# superteensy.net
KiCad netlist of a schematic drawn in EAGLE
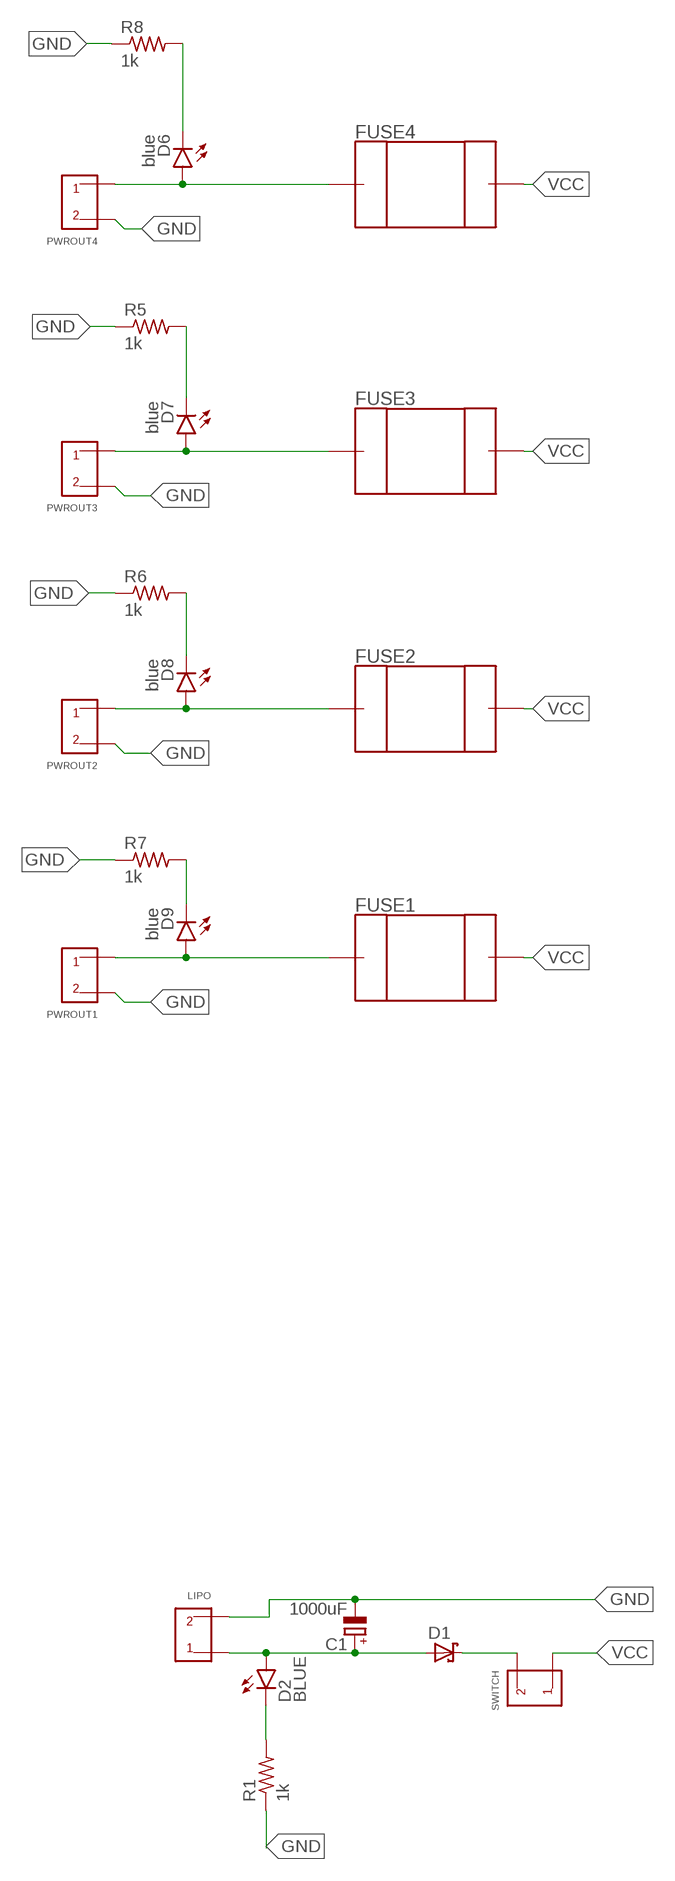
[diagram p0: schematic, sheet 1, part 1 of 2]
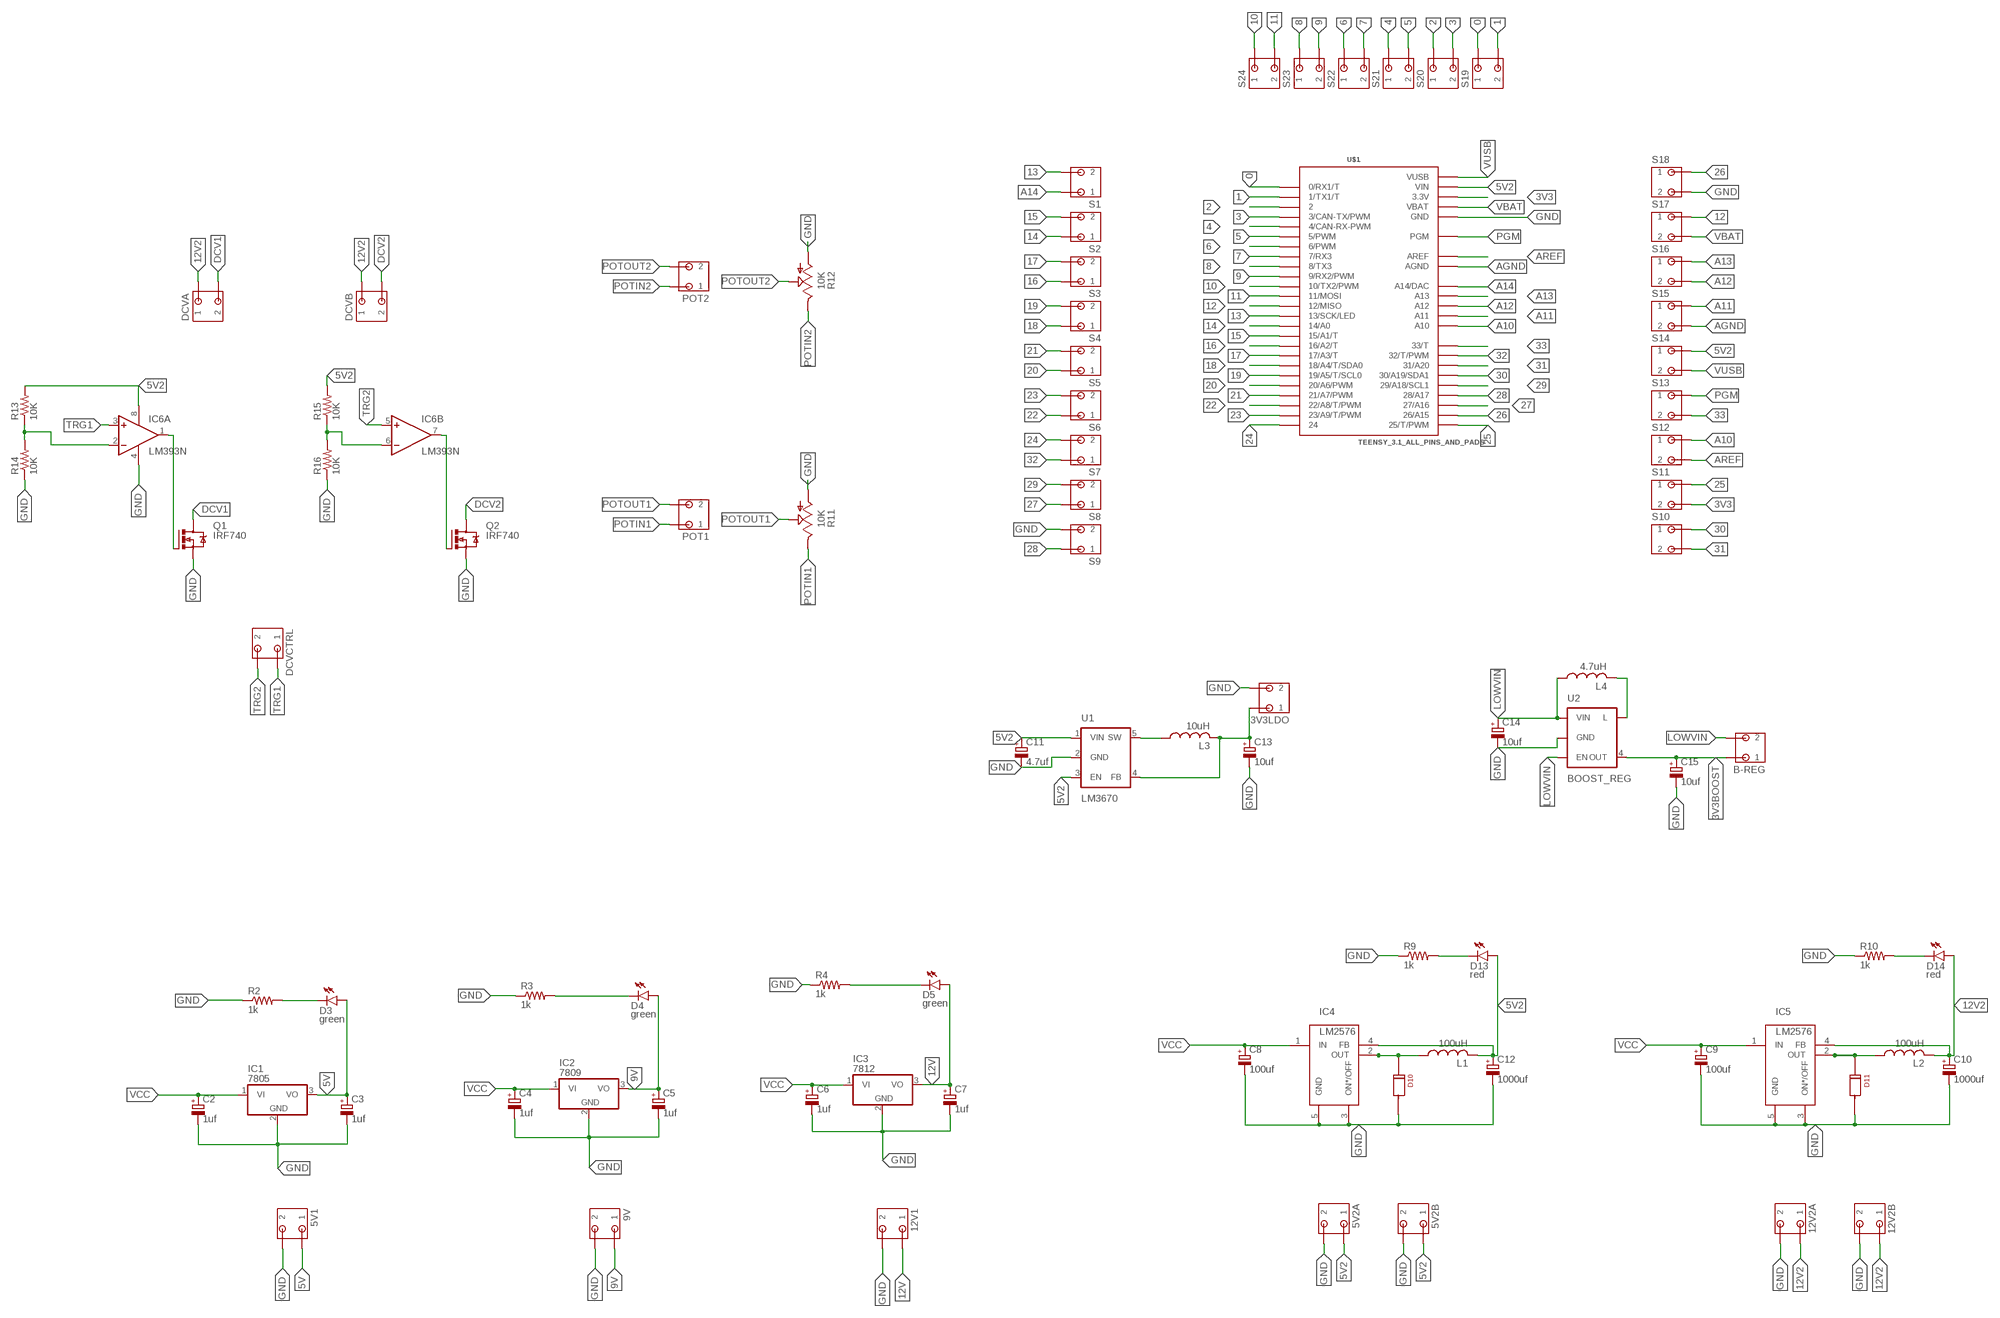
[diagram p1: schematic, sheet 1, part 2 of 2]

(export (version "E")
  (design (tool "Eeschema 10.0.6"))
  (components
    (comp (ref "3V3LDO")
      (value "SPTBA2-B2")
      (footprint "eagle-import:SPTB")
      (libsource (lib "eagle-import") (part "SPTBA2-B2"))
    )
    (comp (ref "5V1")
      (value "SPTBA2-B2")
      (footprint "eagle-import:SPTB")
      (libsource (lib "eagle-import") (part "SPTBA2-B2"))
    )
    (comp (ref "5V2A")
      (value "SPTBA2-B2")
      (footprint "eagle-import:SPTB")
      (libsource (lib "eagle-import") (part "SPTBA2-B2"))
    )
    (comp (ref "5V2B")
      (value "SPTBA2-B2")
      (footprint "eagle-import:SPTB")
      (libsource (lib "eagle-import") (part "SPTBA2-B2"))
    )
    (comp (ref "9V")
      (value "SPTBA2-B2")
      (footprint "eagle-import:SPTB")
      (libsource (lib "eagle-import") (part "SPTBA2-B2"))
    )
    (comp (ref "12V1")
      (value "SPTBA2-B2")
      (footprint "eagle-import:SPTB")
      (libsource (lib "eagle-import") (part "SPTBA2-B2"))
    )
    (comp (ref "12V2A")
      (value "SPTBA2-B2")
      (footprint "eagle-import:SPTB")
      (libsource (lib "eagle-import") (part "SPTBA2-B2"))
    )
    (comp (ref "12V2B")
      (value "SPTBA2-B2")
      (footprint "eagle-import:SPTB")
      (libsource (lib "eagle-import") (part "SPTBA2-B2"))
    )
    (comp (ref "B-REG")
      (value "SPTBA2-B2")
      (footprint "eagle-import:SPTB")
      (libsource (lib "eagle-import") (part "SPTBA2-B2"))
    )
    (comp (ref "C1")
      (value "1000uF")
      (footprint "eagle-import:E7,5-16")
      (libsource (lib "eagle-import") (part "CPOL-EUE7.5-16"))
    )
    (comp (ref "C2")
      (value "1uf")
      (footprint "eagle-import:E2-5")
      (libsource (lib "eagle-import") (part "CPOL-EUE2-5"))
    )
    (comp (ref "C3")
      (value "1uf")
      (footprint "eagle-import:E2-5")
      (libsource (lib "eagle-import") (part "CPOL-EUE2-5"))
    )
    (comp (ref "C4")
      (value "1uf")
      (footprint "eagle-import:E2-5")
      (libsource (lib "eagle-import") (part "CPOL-EUE2-5"))
    )
    (comp (ref "C5")
      (value "1uf")
      (footprint "eagle-import:E2-5")
      (libsource (lib "eagle-import") (part "CPOL-EUE2-5"))
    )
    (comp (ref "C6")
      (value "1uf")
      (footprint "eagle-import:E2-5")
      (libsource (lib "eagle-import") (part "CPOL-EUE2-5"))
    )
    (comp (ref "C7")
      (value "1uf")
      (footprint "eagle-import:E2-5")
      (libsource (lib "eagle-import") (part "CPOL-EUE2-5"))
    )
    (comp (ref "C8")
      (value "100uf")
      (footprint "eagle-import:E2,5-6E")
      (libsource (lib "eagle-import") (part "CPOL-EUE2,5-6E"))
    )
    (comp (ref "C9")
      (value "100uf")
      (footprint "eagle-import:E2,5-6E")
      (libsource (lib "eagle-import") (part "CPOL-EUE2,5-6E"))
    )
    (comp (ref "C10")
      (value "1000uf")
      (footprint "eagle-import:E7,5-16")
      (libsource (lib "eagle-import") (part "CPOL-EUE7.5-16"))
    )
    (comp (ref "C11")
      (value "4.7uf")
      (footprint "eagle-import:E2-5")
      (libsource (lib "eagle-import") (part "CPOL-EUE2-5"))
    )
    (comp (ref "C12")
      (value "1000uf")
      (footprint "eagle-import:E7,5-16")
      (libsource (lib "eagle-import") (part "CPOL-EUE7.5-16"))
    )
    (comp (ref "C13")
      (value "10uf")
      (footprint "eagle-import:E2-5")
      (libsource (lib "eagle-import") (part "CPOL-EUE2-5"))
    )
    (comp (ref "C14")
      (value "10uf")
      (footprint "eagle-import:E2-5")
      (libsource (lib "eagle-import") (part "CPOL-EUE2-5"))
    )
    (comp (ref "C15")
      (value "10uf")
      (footprint "eagle-import:E2-5")
      (libsource (lib "eagle-import") (part "CPOL-EUE2-5"))
    )
    (comp (ref "D1")
      (value "SCHOTTKY-DIODEP6T15")
      (footprint "eagle-import:P6T15")
      (libsource (lib "eagle-import") (part "SCHOTTKY-DIODEP6T15"))
    )
    (comp (ref "D2")
      (value "BLUE")
      (footprint "eagle-import:LED5MM")
      (libsource (lib "eagle-import") (part "LED5MM"))
    )
    (comp (ref "D3")
      (value "green")
      (footprint "eagle-import:LED5MM")
      (libsource (lib "eagle-import") (part "LED5MM"))
    )
    (comp (ref "D4")
      (value "green")
      (footprint "eagle-import:LED5MM")
      (libsource (lib "eagle-import") (part "LED5MM"))
    )
    (comp (ref "D5")
      (value "green")
      (footprint "eagle-import:LED5MM")
      (libsource (lib "eagle-import") (part "LED5MM"))
    )
    (comp (ref "D6")
      (value "blue")
      (footprint "eagle-import:LED5MM")
      (libsource (lib "eagle-import") (part "LED5MM"))
    )
    (comp (ref "D7")
      (value "blue")
      (footprint "eagle-import:LED5MM")
      (libsource (lib "eagle-import") (part "LED5MM"))
    )
    (comp (ref "D8")
      (value "blue")
      (footprint "eagle-import:LED5MM")
      (libsource (lib "eagle-import") (part "LED5MM"))
    )
    (comp (ref "D9")
      (value "blue")
      (footprint "eagle-import:LED5MM")
      (libsource (lib "eagle-import") (part "LED5MM"))
    )
    (comp (ref "D10")
      (value "1N5822")
      (footprint "eagle-import:1N5822")
      (libsource (lib "eagle-import") (part "1N5822"))
    )
    (comp (ref "D11")
      (value "1N5822")
      (footprint "eagle-import:1N5822")
      (libsource (lib "eagle-import") (part "1N5822"))
    )
    (comp (ref "D13")
      (value "red")
      (footprint "eagle-import:LED5MM")
      (libsource (lib "eagle-import") (part "LED5MM"))
    )
    (comp (ref "D14")
      (value "red")
      (footprint "eagle-import:LED5MM")
      (libsource (lib "eagle-import") (part "LED5MM"))
    )
    (comp (ref "DCVA")
      (value "SPTBA2-B2")
      (footprint "eagle-import:SPTB")
      (libsource (lib "eagle-import") (part "SPTBA2-B2"))
    )
    (comp (ref "DCVB")
      (value "SPTBA2-B2")
      (footprint "eagle-import:SPTB")
      (libsource (lib "eagle-import") (part "SPTBA2-B2"))
    )
    (comp (ref "DCVCTRL")
      (value "SPTBA2-B2")
      (footprint "eagle-import:SPTB")
      (libsource (lib "eagle-import") (part "#rcn-15-new-A2-b2-appended_SPTBA2-B2"))
    )
    (comp (ref "FUSE1")
      (value "CPT-FUSE")
      (footprint "eagle-import:CPT-FUSES")
      (libsource (lib "eagle-import") (part "CPT-FUSE"))
    )
    (comp (ref "FUSE2")
      (value "CPT-FUSE")
      (footprint "eagle-import:CPT-FUSES")
      (libsource (lib "eagle-import") (part "CPT-FUSE"))
    )
    (comp (ref "FUSE3")
      (value "CPT-FUSE")
      (footprint "eagle-import:CPT-FUSES")
      (libsource (lib "eagle-import") (part "CPT-FUSE"))
    )
    (comp (ref "FUSE4")
      (value "CPT-FUSE")
      (footprint "eagle-import:CPT-FUSES")
      (libsource (lib "eagle-import") (part "CPT-FUSE"))
    )
    (comp (ref "IC1")
      (value "7805")
      (footprint "eagle-import:78XX")
      (libsource (lib "eagle-import") (part "7805"))
    )
    (comp (ref "IC2")
      (value "7809")
      (footprint "eagle-import:78XX")
      (libsource (lib "eagle-import") (part "7809"))
    )
    (comp (ref "IC3")
      (value "7812")
      (footprint "eagle-import:78XX")
      (libsource (lib "eagle-import") (part "7812"))
    )
    (comp (ref "IC4")
      (value "LM2576")
      (footprint "eagle-import:LM2576")
      (libsource (lib "eagle-import") (part "LM2576"))
    )
    (comp (ref "IC5")
      (value "LM2576")
      (footprint "eagle-import:LM2576")
      (libsource (lib "eagle-import") (part "LM2576"))
    )
    (comp (ref "IC6")
      (value "LM393N")
      (footprint "eagle-import:DIL08")
      (libsource (lib "eagle-import") (part "LM393N"))
    )
    (comp (ref "L1")
      (value "100uH")
      (footprint "eagle-import:0204_7")
      (libsource (lib "eagle-import") (part "L-US0204/7"))
    )
    (comp (ref "L2")
      (value "100uH")
      (footprint "eagle-import:0204_7")
      (libsource (lib "eagle-import") (part "L-US0204/7"))
    )
    (comp (ref "L3")
      (value "10uH")
      (footprint "eagle-import:0204_7")
      (libsource (lib "eagle-import") (part "L-US0204/7"))
    )
    (comp (ref "L4")
      (value "4.7uH")
      (footprint "eagle-import:0204_7")
      (libsource (lib "eagle-import") (part "L-US0204/7"))
    )
    (comp (ref "LIPO")
      (value "SCREW_XT-60")
      (footprint "eagle-import:SCREW_XT-60")
      (libsource (lib "eagle-import") (part "SCREW_XT-60"))
    )
    (comp (ref "POT1")
      (value "SPTBA2-B2")
      (footprint "eagle-import:SPTB")
      (libsource (lib "eagle-import") (part "SPTBA2-B2"))
    )
    (comp (ref "POT2")
      (value "SPTBA2-B2")
      (footprint "eagle-import:SPTB")
      (libsource (lib "eagle-import") (part "SPTBA2-B2"))
    )
    (comp (ref "PWROUT1")
      (value "SCREW_XT-60")
      (footprint "eagle-import:SCREW_XT-60")
      (libsource (lib "eagle-import") (part "SCREW_XT-60"))
    )
    (comp (ref "PWROUT2")
      (value "SCREW_XT-60")
      (footprint "eagle-import:SCREW_XT-60")
      (libsource (lib "eagle-import") (part "SCREW_XT-60"))
    )
    (comp (ref "PWROUT3")
      (value "SCREW_XT-60")
      (footprint "eagle-import:SCREW_XT-60")
      (libsource (lib "eagle-import") (part "SCREW_XT-60"))
    )
    (comp (ref "PWROUT4")
      (value "SCREW_XT-60")
      (footprint "eagle-import:SCREW_XT-60")
      (libsource (lib "eagle-import") (part "SCREW_XT-60"))
    )
    (comp (ref "Q1")
      (value "IRF740")
      (footprint "eagle-import:TO220BV")
      (libsource (lib "eagle-import") (part "IRF740"))
    )
    (comp (ref "Q2")
      (value "IRF740")
      (footprint "eagle-import:TO220BV")
      (libsource (lib "eagle-import") (part "IRF740"))
    )
    (comp (ref "R1")
      (value "1k")
      (footprint "eagle-import:0204_7")
      (libsource (lib "eagle-import") (part "R-US_0204/7"))
    )
    (comp (ref "R2")
      (value "1k")
      (footprint "eagle-import:0204_7")
      (libsource (lib "eagle-import") (part "R-US_0204/7"))
    )
    (comp (ref "R3")
      (value "1k")
      (footprint "eagle-import:0204_7")
      (libsource (lib "eagle-import") (part "R-US_0204/7"))
    )
    (comp (ref "R4")
      (value "1k")
      (footprint "eagle-import:0204_7")
      (libsource (lib "eagle-import") (part "R-US_0204/7"))
    )
    (comp (ref "R5")
      (value "1k")
      (footprint "eagle-import:0204_7")
      (libsource (lib "eagle-import") (part "R-US_0204/7"))
    )
    (comp (ref "R6")
      (value "1k")
      (footprint "eagle-import:0204_7")
      (libsource (lib "eagle-import") (part "R-US_0204/7"))
    )
    (comp (ref "R7")
      (value "1k")
      (footprint "eagle-import:0204_7")
      (libsource (lib "eagle-import") (part "R-US_0204/7"))
    )
    (comp (ref "R8")
      (value "1k")
      (footprint "eagle-import:0204_7")
      (libsource (lib "eagle-import") (part "R-US_0204/7"))
    )
    (comp (ref "R9")
      (value "1k")
      (footprint "eagle-import:0204_7")
      (libsource (lib "eagle-import") (part "R-US_0204/7"))
    )
    (comp (ref "R10")
      (value "1k")
      (footprint "eagle-import:0204_7")
      (libsource (lib "eagle-import") (part "R-US_0204/7"))
    )
    (comp (ref "R11")
      (value "10K")
      (footprint "eagle-import:CA6V")
      (libsource (lib "eagle-import") (part "TRIM_US-CA6V"))
    )
    (comp (ref "R12")
      (value "10K")
      (footprint "eagle-import:CA6V")
      (libsource (lib "eagle-import") (part "TRIM_US-CA6V"))
    )
    (comp (ref "R13")
      (value "10K")
      (footprint "eagle-import:0204_7")
      (libsource (lib "eagle-import") (part "R-US_0204/7"))
    )
    (comp (ref "R14")
      (value "10K")
      (footprint "eagle-import:0204_7")
      (libsource (lib "eagle-import") (part "R-US_0204/7"))
    )
    (comp (ref "R15")
      (value "10K")
      (footprint "eagle-import:0204_7")
      (libsource (lib "eagle-import") (part "R-US_0204/7"))
    )
    (comp (ref "R16")
      (value "10K")
      (footprint "eagle-import:0204_7")
      (libsource (lib "eagle-import") (part "R-US_0204/7"))
    )
    (comp (ref "S1")
      (value "SPTBA2-B2")
      (footprint "eagle-import:SPTB")
      (libsource (lib "eagle-import") (part "SPTBA2-B2"))
    )
    (comp (ref "S2")
      (value "SPTBA2-B2")
      (footprint "eagle-import:SPTB")
      (libsource (lib "eagle-import") (part "SPTBA2-B2"))
    )
    (comp (ref "S3")
      (value "SPTBA2-B2")
      (footprint "eagle-import:SPTB")
      (libsource (lib "eagle-import") (part "SPTBA2-B2"))
    )
    (comp (ref "S4")
      (value "SPTBA2-B2")
      (footprint "eagle-import:SPTB")
      (libsource (lib "eagle-import") (part "SPTBA2-B2"))
    )
    (comp (ref "S5")
      (value "SPTBA2-B2")
      (footprint "eagle-import:SPTB")
      (libsource (lib "eagle-import") (part "SPTBA2-B2"))
    )
    (comp (ref "S6")
      (value "SPTBA2-B2")
      (footprint "eagle-import:SPTB")
      (libsource (lib "eagle-import") (part "SPTBA2-B2"))
    )
    (comp (ref "S7")
      (value "SPTBA2-B2")
      (footprint "eagle-import:SPTB")
      (libsource (lib "eagle-import") (part "SPTBA2-B2"))
    )
    (comp (ref "S8")
      (value "SPTBA2-B2")
      (footprint "eagle-import:SPTB")
      (libsource (lib "eagle-import") (part "SPTBA2-B2"))
    )
    (comp (ref "S9")
      (value "SPTBA2-B2")
      (footprint "eagle-import:SPTB")
      (libsource (lib "eagle-import") (part "SPTBA2-B2"))
    )
    (comp (ref "S10")
      (value "SPTBA2-B2")
      (footprint "eagle-import:SPTB")
      (libsource (lib "eagle-import") (part "SPTBA2-B2"))
    )
    (comp (ref "S11")
      (value "SPTBA2-B2")
      (footprint "eagle-import:SPTB")
      (libsource (lib "eagle-import") (part "SPTBA2-B2"))
    )
    (comp (ref "S12")
      (value "SPTBA2-B2")
      (footprint "eagle-import:SPTB")
      (libsource (lib "eagle-import") (part "SPTBA2-B2"))
    )
    (comp (ref "S13")
      (value "SPTBA2-B2")
      (footprint "eagle-import:SPTB")
      (libsource (lib "eagle-import") (part "SPTBA2-B2"))
    )
    (comp (ref "S14")
      (value "SPTBA2-B2")
      (footprint "eagle-import:SPTB")
      (libsource (lib "eagle-import") (part "SPTBA2-B2"))
    )
    (comp (ref "S15")
      (value "SPTBA2-B2")
      (footprint "eagle-import:SPTB")
      (libsource (lib "eagle-import") (part "SPTBA2-B2"))
    )
    (comp (ref "S16")
      (value "SPTBA2-B2")
      (footprint "eagle-import:SPTB")
      (libsource (lib "eagle-import") (part "SPTBA2-B2"))
    )
    (comp (ref "S17")
      (value "SPTBA2-B2")
      (footprint "eagle-import:SPTB")
      (libsource (lib "eagle-import") (part "SPTBA2-B2"))
    )
    (comp (ref "S18")
      (value "SPTBA2-B2")
      (footprint "eagle-import:SPTB")
      (libsource (lib "eagle-import") (part "SPTBA2-B2"))
    )
    (comp (ref "S19")
      (value "SPTBA2-B2")
      (footprint "eagle-import:SPTB")
      (libsource (lib "eagle-import") (part "SPTBA2-B2"))
    )
    (comp (ref "S20")
      (value "SPTBA2-B2")
      (footprint "eagle-import:SPTB")
      (libsource (lib "eagle-import") (part "SPTBA2-B2"))
    )
    (comp (ref "S21")
      (value "SPTBA2-B2")
      (footprint "eagle-import:SPTB")
      (libsource (lib "eagle-import") (part "SPTBA2-B2"))
    )
    (comp (ref "S22")
      (value "SPTBA2-B2")
      (footprint "eagle-import:SPTB")
      (libsource (lib "eagle-import") (part "SPTBA2-B2"))
    )
    (comp (ref "S23")
      (value "SPTBA2-B2")
      (footprint "eagle-import:SPTB")
      (libsource (lib "eagle-import") (part "SPTBA2-B2"))
    )
    (comp (ref "S24")
      (value "SPTBA2-B2")
      (footprint "eagle-import:SPTB")
      (libsource (lib "eagle-import") (part "SPTBA2-B2"))
    )
    (comp (ref "SWITCH")
      (value "SCREW_XT-60")
      (footprint "eagle-import:SCREW_XT-60")
      (libsource (lib "eagle-import") (part "SCREW_XT-60"))
    )
    (comp (ref "U$1")
      (value "TEENSY_3.1_ALL_PINS_AND_PADS")
      (footprint "eagle-import:TEENSY_3.1_ALLPINS")
      (libsource (lib "eagle-import") (part "TEENSY_3.1_ALL_PINS_AND_PADS"))
    )
    (comp (ref "U1")
      (value "LM3670")
      (footprint "eagle-import:SOT23-5")
      (libsource (lib "eagle-import") (part "V_REG_LDOSMD"))
    )
    (comp (ref "U2")
      (value "BOOST_REG")
      (footprint "eagle-import:SOT23-5")
      (libsource (lib "eagle-import") (part "synchronous-boot-regulator-TPS61097A-33_V_REG_LDOSMD"))
    )
  )
  (nets
    (net (code "1") (name "0") (class "Default")
      (node (ref "S19") (pin "A1") (pinfunction "1_A1") (pintype "bidirectional"))
      (node (ref "S19") (pin "A2") (pinfunction "1_A2") (pintype "bidirectional"))
      (node (ref "U$1") (pin "0") (pinfunction "0/RX1/T_0") (pintype "bidirectional"))
    )
    (net (code "2") (name "1") (class "Default")
      (node (ref "S19") (pin "B1") (pinfunction "2_B1") (pintype "bidirectional"))
      (node (ref "S19") (pin "B2") (pinfunction "2_B2") (pintype "bidirectional"))
      (node (ref "U$1") (pin "1") (pinfunction "1/TX1/T_1") (pintype "bidirectional"))
    )
    (net (code "3") (name "2") (class "Default")
      (node (ref "S20") (pin "A1") (pinfunction "1_A1") (pintype "bidirectional"))
      (node (ref "S20") (pin "A2") (pinfunction "1_A2") (pintype "bidirectional"))
      (node (ref "U$1") (pin "2") (pinfunction "2_2") (pintype "bidirectional"))
    )
    (net (code "4") (name "3") (class "Default")
      (node (ref "S20") (pin "B1") (pinfunction "2_B1") (pintype "bidirectional"))
      (node (ref "S20") (pin "B2") (pinfunction "2_B2") (pintype "bidirectional"))
      (node (ref "U$1") (pin "3") (pinfunction "3/CAN-TX/PWM_3") (pintype "bidirectional"))
    )
    (net (code "5") (name "3V3") (class "Default")
      (node (ref "S11") (pin "B1") (pinfunction "2_B1") (pintype "bidirectional"))
      (node (ref "S11") (pin "B2") (pinfunction "2_B2") (pintype "bidirectional"))
      (node (ref "U$1") (pin "3.3V") (pinfunction "3.3V_3.3V") (pintype "power_in"))
      (node (ref "U$1") (pin "3.3V1") (pinfunction "3.3V_3.3V1") (pintype "power_in"))
      (node (ref "U$1") (pin "3.3V2") (pinfunction "3.3V_3.3V2") (pintype "power_in"))
    )
    (net (code "6") (name "3V3BOOST") (class "Default")
      (node (ref "B-REG") (pin "A1") (pinfunction "1_A1") (pintype "bidirectional"))
      (node (ref "B-REG") (pin "A2") (pinfunction "1_A2") (pintype "bidirectional"))
      (node (ref "C15") (pin "+") (pinfunction "+_+") (pintype "passive"))
      (node (ref "U2") (pin "4") (pinfunction "OUT_4") (pintype "input"))
    )
    (net (code "7") (name "4") (class "Default")
      (node (ref "S21") (pin "A1") (pinfunction "1_A1") (pintype "bidirectional"))
      (node (ref "S21") (pin "A2") (pinfunction "1_A2") (pintype "bidirectional"))
      (node (ref "U$1") (pin "4") (pinfunction "4/CAN-RX-PWM_4") (pintype "bidirectional"))
    )
    (net (code "8") (name "5") (class "Default")
      (node (ref "S21") (pin "B1") (pinfunction "2_B1") (pintype "bidirectional"))
      (node (ref "S21") (pin "B2") (pinfunction "2_B2") (pintype "bidirectional"))
      (node (ref "U$1") (pin "5") (pinfunction "5/PWM_5") (pintype "bidirectional"))
    )
    (net (code "9") (name "5V") (class "Default")
      (node (ref "5V1") (pin "A1") (pinfunction "1_A1") (pintype "bidirectional"))
      (node (ref "5V1") (pin "A2") (pinfunction "1_A2") (pintype "bidirectional"))
      (node (ref "C3") (pin "+") (pinfunction "+_+") (pintype "passive"))
      (node (ref "D3") (pin "A") (pinfunction "A_A") (pintype "passive"))
      (node (ref "IC1") (pin "3") (pinfunction "VO_3") (pintype "passive"))
    )
    (net (code "10") (name "5V2") (class "Default")
      (node (ref "5V2A") (pin "A1") (pinfunction "1_A1") (pintype "bidirectional"))
      (node (ref "5V2A") (pin "A2") (pinfunction "1_A2") (pintype "bidirectional"))
      (node (ref "5V2B") (pin "A1") (pinfunction "1_A1") (pintype "bidirectional"))
      (node (ref "5V2B") (pin "A2") (pinfunction "1_A2") (pintype "bidirectional"))
      (node (ref "C11") (pin "+") (pinfunction "+_+") (pintype "passive"))
      (node (ref "C12") (pin "+") (pinfunction "+_+") (pintype "passive"))
      (node (ref "D13") (pin "A") (pinfunction "A_A") (pintype "passive"))
      (node (ref "IC4") (pin "4") (pinfunction "FB_4") (pintype "bidirectional"))
      (node (ref "IC6") (pin "8") (pinfunction "V+_8") (pintype "power_in"))
      (node (ref "L1") (pin "2") (pinfunction "2_2") (pintype "passive"))
      (node (ref "R13") (pin "2") (pinfunction "2_2") (pintype "passive"))
      (node (ref "R15") (pin "2") (pinfunction "2_2") (pintype "passive"))
      (node (ref "S14") (pin "A1") (pinfunction "1_A1") (pintype "bidirectional"))
      (node (ref "S14") (pin "A2") (pinfunction "1_A2") (pintype "bidirectional"))
      (node (ref "U$1") (pin "VIN") (pinfunction "VIN_VIN") (pintype "power_in"))
      (node (ref "U1") (pin "1") (pinfunction "VIN_1") (pintype "input"))
      (node (ref "U1") (pin "3") (pinfunction "EN_3") (pintype "input"))
    )
    (net (code "11") (name "6") (class "Default")
      (node (ref "S22") (pin "A1") (pinfunction "1_A1") (pintype "bidirectional"))
      (node (ref "S22") (pin "A2") (pinfunction "1_A2") (pintype "bidirectional"))
      (node (ref "U$1") (pin "6") (pinfunction "6/PWM_6") (pintype "bidirectional"))
    )
    (net (code "12") (name "7") (class "Default")
      (node (ref "S22") (pin "B1") (pinfunction "2_B1") (pintype "bidirectional"))
      (node (ref "S22") (pin "B2") (pinfunction "2_B2") (pintype "bidirectional"))
      (node (ref "U$1") (pin "7") (pinfunction "7/RX3_7") (pintype "bidirectional"))
    )
    (net (code "13") (name "8") (class "Default")
      (node (ref "S23") (pin "A1") (pinfunction "1_A1") (pintype "bidirectional"))
      (node (ref "S23") (pin "A2") (pinfunction "1_A2") (pintype "bidirectional"))
      (node (ref "U$1") (pin "8") (pinfunction "8/TX3_8") (pintype "bidirectional"))
    )
    (net (code "14") (name "9") (class "Default")
      (node (ref "S23") (pin "B1") (pinfunction "2_B1") (pintype "bidirectional"))
      (node (ref "S23") (pin "B2") (pinfunction "2_B2") (pintype "bidirectional"))
      (node (ref "U$1") (pin "9") (pinfunction "9/RX2/PWM_9") (pintype "bidirectional"))
    )
    (net (code "15") (name "9V") (class "Default")
      (node (ref "9V") (pin "A1") (pinfunction "1_A1") (pintype "bidirectional"))
      (node (ref "9V") (pin "A2") (pinfunction "1_A2") (pintype "bidirectional"))
      (node (ref "C5") (pin "+") (pinfunction "+_+") (pintype "passive"))
      (node (ref "D4") (pin "A") (pinfunction "A_A") (pintype "passive"))
      (node (ref "IC2") (pin "3") (pinfunction "VO_3") (pintype "passive"))
    )
    (net (code "16") (name "10") (class "Default")
      (node (ref "S24") (pin "A1") (pinfunction "1_A1") (pintype "bidirectional"))
      (node (ref "S24") (pin "A2") (pinfunction "1_A2") (pintype "bidirectional"))
      (node (ref "U$1") (pin "10") (pinfunction "10/TX2/PWM_10") (pintype "bidirectional"))
    )
    (net (code "17") (name "11") (class "Default")
      (node (ref "S24") (pin "B1") (pinfunction "2_B1") (pintype "bidirectional"))
      (node (ref "S24") (pin "B2") (pinfunction "2_B2") (pintype "bidirectional"))
      (node (ref "U$1") (pin "11") (pinfunction "11/MOSI_11") (pintype "bidirectional"))
    )
    (net (code "18") (name "12") (class "Default")
      (node (ref "S17") (pin "A1") (pinfunction "1_A1") (pintype "bidirectional"))
      (node (ref "S17") (pin "A2") (pinfunction "1_A2") (pintype "bidirectional"))
      (node (ref "U$1") (pin "12") (pinfunction "12/MISO_12") (pintype "bidirectional"))
    )
    (net (code "19") (name "12V") (class "Default")
      (node (ref "12V1") (pin "A1") (pinfunction "1_A1") (pintype "bidirectional"))
      (node (ref "12V1") (pin "A2") (pinfunction "1_A2") (pintype "bidirectional"))
      (node (ref "C7") (pin "+") (pinfunction "+_+") (pintype "passive"))
      (node (ref "D5") (pin "A") (pinfunction "A_A") (pintype "passive"))
      (node (ref "IC3") (pin "3") (pinfunction "VO_3") (pintype "passive"))
    )
    (net (code "20") (name "12V2") (class "Default")
      (node (ref "12V2A") (pin "A1") (pinfunction "1_A1") (pintype "bidirectional"))
      (node (ref "12V2A") (pin "A2") (pinfunction "1_A2") (pintype "bidirectional"))
      (node (ref "12V2B") (pin "A1") (pinfunction "1_A1") (pintype "bidirectional"))
      (node (ref "12V2B") (pin "A2") (pinfunction "1_A2") (pintype "bidirectional"))
      (node (ref "C10") (pin "+") (pinfunction "+_+") (pintype "passive"))
      (node (ref "D14") (pin "A") (pinfunction "A_A") (pintype "passive"))
      (node (ref "DCVA") (pin "A1") (pinfunction "1_A1") (pintype "bidirectional"))
      (node (ref "DCVA") (pin "A2") (pinfunction "1_A2") (pintype "bidirectional"))
      (node (ref "DCVB") (pin "A1") (pinfunction "1_A1") (pintype "bidirectional"))
      (node (ref "DCVB") (pin "A2") (pinfunction "1_A2") (pintype "bidirectional"))
      (node (ref "IC5") (pin "4") (pinfunction "FB_4") (pintype "bidirectional"))
      (node (ref "L2") (pin "2") (pinfunction "2_2") (pintype "passive"))
    )
    (net (code "21") (name "13") (class "Default")
      (node (ref "S1") (pin "B1") (pinfunction "2_B1") (pintype "bidirectional"))
      (node (ref "S1") (pin "B2") (pinfunction "2_B2") (pintype "bidirectional"))
      (node (ref "U$1") (pin "13") (pinfunction "13/SCK/LED_13") (pintype "bidirectional"))
    )
    (net (code "22") (name "14") (class "Default")
      (node (ref "S2") (pin "A1") (pinfunction "1_A1") (pintype "bidirectional"))
      (node (ref "S2") (pin "A2") (pinfunction "1_A2") (pintype "bidirectional"))
      (node (ref "U$1") (pin "14/A0") (pinfunction "14/A0_14/A0") (pintype "bidirectional"))
    )
    (net (code "23") (name "15") (class "Default")
      (node (ref "S2") (pin "B1") (pinfunction "2_B1") (pintype "bidirectional"))
      (node (ref "S2") (pin "B2") (pinfunction "2_B2") (pintype "bidirectional"))
      (node (ref "U$1") (pin "15/A1") (pinfunction "15/A1/T_15/A1") (pintype "bidirectional"))
    )
    (net (code "24") (name "16") (class "Default")
      (node (ref "S3") (pin "A1") (pinfunction "1_A1") (pintype "bidirectional"))
      (node (ref "S3") (pin "A2") (pinfunction "1_A2") (pintype "bidirectional"))
      (node (ref "U$1") (pin "16/A2") (pinfunction "16/A2/T_16/A2") (pintype "bidirectional"))
    )
    (net (code "25") (name "17") (class "Default")
      (node (ref "S3") (pin "B1") (pinfunction "2_B1") (pintype "bidirectional"))
      (node (ref "S3") (pin "B2") (pinfunction "2_B2") (pintype "bidirectional"))
      (node (ref "U$1") (pin "17/A3") (pinfunction "17/A3/T_17/A3") (pintype "bidirectional"))
    )
    (net (code "26") (name "18") (class "Default")
      (node (ref "S4") (pin "A1") (pinfunction "1_A1") (pintype "bidirectional"))
      (node (ref "S4") (pin "A2") (pinfunction "1_A2") (pintype "bidirectional"))
      (node (ref "U$1") (pin "18/A4") (pinfunction "18/A4/T/SDA0_18/A4") (pintype "bidirectional"))
    )
    (net (code "27") (name "19") (class "Default")
      (node (ref "S4") (pin "B1") (pinfunction "2_B1") (pintype "bidirectional"))
      (node (ref "S4") (pin "B2") (pinfunction "2_B2") (pintype "bidirectional"))
      (node (ref "U$1") (pin "19/A5") (pinfunction "19/A5/T/SCL0_19/A5") (pintype "bidirectional"))
    )
    (net (code "28") (name "20") (class "Default")
      (node (ref "S5") (pin "A1") (pinfunction "1_A1") (pintype "bidirectional"))
      (node (ref "S5") (pin "A2") (pinfunction "1_A2") (pintype "bidirectional"))
      (node (ref "U$1") (pin "20/A6") (pinfunction "20/A6/PWM_20/A6") (pintype "bidirectional"))
    )
    (net (code "29") (name "21") (class "Default")
      (node (ref "S5") (pin "B1") (pinfunction "2_B1") (pintype "bidirectional"))
      (node (ref "S5") (pin "B2") (pinfunction "2_B2") (pintype "bidirectional"))
      (node (ref "U$1") (pin "21/A7") (pinfunction "21/A7/PWM_21/A7") (pintype "bidirectional"))
    )
    (net (code "30") (name "22") (class "Default")
      (node (ref "S6") (pin "A1") (pinfunction "1_A1") (pintype "bidirectional"))
      (node (ref "S6") (pin "A2") (pinfunction "1_A2") (pintype "bidirectional"))
      (node (ref "U$1") (pin "22/A8") (pinfunction "22/A8/T/PWM_22/A8") (pintype "bidirectional"))
    )
    (net (code "31") (name "23") (class "Default")
      (node (ref "S6") (pin "B1") (pinfunction "2_B1") (pintype "bidirectional"))
      (node (ref "S6") (pin "B2") (pinfunction "2_B2") (pintype "bidirectional"))
      (node (ref "U$1") (pin "23/A9") (pinfunction "23/A9/T/PWM_23/A9") (pintype "bidirectional"))
    )
    (net (code "32") (name "24") (class "Default")
      (node (ref "S7") (pin "B1") (pinfunction "2_B1") (pintype "bidirectional"))
      (node (ref "S7") (pin "B2") (pinfunction "2_B2") (pintype "bidirectional"))
      (node (ref "U$1") (pin "24") (pinfunction "24_24") (pintype "bidirectional"))
    )
    (net (code "33") (name "25") (class "Default")
      (node (ref "S11") (pin "A1") (pinfunction "1_A1") (pintype "bidirectional"))
      (node (ref "S11") (pin "A2") (pinfunction "1_A2") (pintype "bidirectional"))
      (node (ref "U$1") (pin "25") (pinfunction "25/T/PWM_25") (pintype "bidirectional"))
    )
    (net (code "34") (name "26") (class "Default")
      (node (ref "S18") (pin "A1") (pinfunction "1_A1") (pintype "bidirectional"))
      (node (ref "S18") (pin "A2") (pinfunction "1_A2") (pintype "bidirectional"))
      (node (ref "U$1") (pin "26") (pinfunction "26/A15_26") (pintype "bidirectional"))
    )
    (net (code "35") (name "27") (class "Default")
      (node (ref "S8") (pin "A1") (pinfunction "1_A1") (pintype "bidirectional"))
      (node (ref "S8") (pin "A2") (pinfunction "1_A2") (pintype "bidirectional"))
      (node (ref "U$1") (pin "27") (pinfunction "27/A16_27") (pintype "bidirectional"))
    )
    (net (code "36") (name "28") (class "Default")
      (node (ref "S9") (pin "A1") (pinfunction "1_A1") (pintype "bidirectional"))
      (node (ref "S9") (pin "A2") (pinfunction "1_A2") (pintype "bidirectional"))
      (node (ref "U$1") (pin "28") (pinfunction "28/A17_28") (pintype "bidirectional"))
    )
    (net (code "37") (name "29") (class "Default")
      (node (ref "S8") (pin "B1") (pinfunction "2_B1") (pintype "bidirectional"))
      (node (ref "S8") (pin "B2") (pinfunction "2_B2") (pintype "bidirectional"))
      (node (ref "U$1") (pin "29") (pinfunction "29/A18/SCL1_29") (pintype "bidirectional"))
    )
    (net (code "38") (name "30") (class "Default")
      (node (ref "S10") (pin "A1") (pinfunction "1_A1") (pintype "bidirectional"))
      (node (ref "S10") (pin "A2") (pinfunction "1_A2") (pintype "bidirectional"))
      (node (ref "U$1") (pin "30") (pinfunction "30/A19/SDA1_30") (pintype "bidirectional"))
    )
    (net (code "39") (name "31") (class "Default")
      (node (ref "S10") (pin "B1") (pinfunction "2_B1") (pintype "bidirectional"))
      (node (ref "S10") (pin "B2") (pinfunction "2_B2") (pintype "bidirectional"))
      (node (ref "U$1") (pin "31") (pinfunction "31/A20_31") (pintype "bidirectional"))
    )
    (net (code "40") (name "32") (class "Default")
      (node (ref "S7") (pin "A1") (pinfunction "1_A1") (pintype "bidirectional"))
      (node (ref "S7") (pin "A2") (pinfunction "1_A2") (pintype "bidirectional"))
      (node (ref "U$1") (pin "32") (pinfunction "32/T/PWM_32") (pintype "bidirectional"))
    )
    (net (code "41") (name "33") (class "Default")
      (node (ref "S13") (pin "B1") (pinfunction "2_B1") (pintype "bidirectional"))
      (node (ref "S13") (pin "B2") (pinfunction "2_B2") (pintype "bidirectional"))
      (node (ref "U$1") (pin "33") (pinfunction "33/T_33") (pintype "bidirectional"))
    )
    (net (code "42") (name "A10") (class "Default")
      (node (ref "S12") (pin "A1") (pinfunction "1_A1") (pintype "bidirectional"))
      (node (ref "S12") (pin "A2") (pinfunction "1_A2") (pintype "bidirectional"))
      (node (ref "U$1") (pin "A10") (pinfunction "A10_A10") (pintype "bidirectional"))
    )
    (net (code "43") (name "A11") (class "Default")
      (node (ref "S15") (pin "A1") (pinfunction "1_A1") (pintype "bidirectional"))
      (node (ref "S15") (pin "A2") (pinfunction "1_A2") (pintype "bidirectional"))
      (node (ref "U$1") (pin "A11") (pinfunction "A11_A11") (pintype "bidirectional"))
    )
    (net (code "44") (name "A12") (class "Default")
      (node (ref "S16") (pin "B1") (pinfunction "2_B1") (pintype "bidirectional"))
      (node (ref "S16") (pin "B2") (pinfunction "2_B2") (pintype "bidirectional"))
      (node (ref "U$1") (pin "A12") (pinfunction "A12_A12") (pintype "bidirectional"))
    )
    (net (code "45") (name "A13") (class "Default")
      (node (ref "S16") (pin "A1") (pinfunction "1_A1") (pintype "bidirectional"))
      (node (ref "S16") (pin "A2") (pinfunction "1_A2") (pintype "bidirectional"))
      (node (ref "U$1") (pin "A13") (pinfunction "A13_A13") (pintype "bidirectional"))
    )
    (net (code "46") (name "A14") (class "Default")
      (node (ref "S1") (pin "A1") (pinfunction "1_A1") (pintype "bidirectional"))
      (node (ref "S1") (pin "A2") (pinfunction "1_A2") (pintype "bidirectional"))
      (node (ref "U$1") (pin "A14") (pinfunction "A14/DAC_A14") (pintype "bidirectional"))
    )
    (net (code "47") (name "AGND") (class "Default")
      (node (ref "S15") (pin "B1") (pinfunction "2_B1") (pintype "bidirectional"))
      (node (ref "S15") (pin "B2") (pinfunction "2_B2") (pintype "bidirectional"))
      (node (ref "U$1") (pin "AGND") (pinfunction "AGND_AGND") (pintype "power_in"))
    )
    (net (code "48") (name "AREF") (class "Default")
      (node (ref "S12") (pin "B1") (pinfunction "2_B1") (pintype "bidirectional"))
      (node (ref "S12") (pin "B2") (pinfunction "2_B2") (pintype "bidirectional"))
      (node (ref "U$1") (pin "AREF") (pinfunction "AREF_AREF") (pintype "power_in"))
    )
    (net (code "49") (name "DCV1") (class "Default")
      (node (ref "DCVA") (pin "B1") (pinfunction "2_B1") (pintype "bidirectional"))
      (node (ref "DCVA") (pin "B2") (pinfunction "2_B2") (pintype "bidirectional"))
      (node (ref "Q1") (pin "D") (pinfunction "D_D") (pintype "passive"))
    )
    (net (code "50") (name "DCV2") (class "Default")
      (node (ref "DCVB") (pin "B1") (pinfunction "2_B1") (pintype "bidirectional"))
      (node (ref "DCVB") (pin "B2") (pinfunction "2_B2") (pintype "bidirectional"))
      (node (ref "Q2") (pin "D") (pinfunction "D_D") (pintype "passive"))
    )
    (net (code "51") (name "GND") (class "Default")
      (node (ref "12V1") (pin "B1") (pinfunction "2_B1") (pintype "bidirectional"))
      (node (ref "12V1") (pin "B2") (pinfunction "2_B2") (pintype "bidirectional"))
      (node (ref "12V2A") (pin "B1") (pinfunction "2_B1") (pintype "bidirectional"))
      (node (ref "12V2A") (pin "B2") (pinfunction "2_B2") (pintype "bidirectional"))
      (node (ref "12V2B") (pin "B1") (pinfunction "2_B1") (pintype "bidirectional"))
      (node (ref "12V2B") (pin "B2") (pinfunction "2_B2") (pintype "bidirectional"))
      (node (ref "3V3LDO") (pin "B1") (pinfunction "2_B1") (pintype "bidirectional"))
      (node (ref "3V3LDO") (pin "B2") (pinfunction "2_B2") (pintype "bidirectional"))
      (node (ref "5V1") (pin "B1") (pinfunction "2_B1") (pintype "bidirectional"))
      (node (ref "5V1") (pin "B2") (pinfunction "2_B2") (pintype "bidirectional"))
      (node (ref "5V2A") (pin "B1") (pinfunction "2_B1") (pintype "bidirectional"))
      (node (ref "5V2A") (pin "B2") (pinfunction "2_B2") (pintype "bidirectional"))
      (node (ref "5V2B") (pin "B1") (pinfunction "2_B1") (pintype "bidirectional"))
      (node (ref "5V2B") (pin "B2") (pinfunction "2_B2") (pintype "bidirectional"))
      (node (ref "9V") (pin "B1") (pinfunction "2_B1") (pintype "bidirectional"))
      (node (ref "9V") (pin "B2") (pinfunction "2_B2") (pintype "bidirectional"))
      (node (ref "C1") (pin "-") (pinfunction "-_-") (pintype "passive"))
      (node (ref "C10") (pin "-") (pinfunction "-_-") (pintype "passive"))
      (node (ref "C11") (pin "-") (pinfunction "-_-") (pintype "passive"))
      (node (ref "C12") (pin "-") (pinfunction "-_-") (pintype "passive"))
      (node (ref "C13") (pin "-") (pinfunction "-_-") (pintype "passive"))
      (node (ref "C14") (pin "-") (pinfunction "-_-") (pintype "passive"))
      (node (ref "C15") (pin "-") (pinfunction "-_-") (pintype "passive"))
      (node (ref "C2") (pin "-") (pinfunction "-_-") (pintype "passive"))
      (node (ref "C3") (pin "-") (pinfunction "-_-") (pintype "passive"))
      (node (ref "C4") (pin "-") (pinfunction "-_-") (pintype "passive"))
      (node (ref "C5") (pin "-") (pinfunction "-_-") (pintype "passive"))
      (node (ref "C6") (pin "-") (pinfunction "-_-") (pintype "passive"))
      (node (ref "C7") (pin "-") (pinfunction "-_-") (pintype "passive"))
      (node (ref "C8") (pin "-") (pinfunction "-_-") (pintype "passive"))
      (node (ref "C9") (pin "-") (pinfunction "-_-") (pintype "passive"))
      (node (ref "D10") (pin "-") (pinfunction "-_-") (pintype "bidirectional"))
      (node (ref "D11") (pin "-") (pinfunction "-_-") (pintype "bidirectional"))
      (node (ref "IC1") (pin "2") (pinfunction "GND_2") (pintype "passive"))
      (node (ref "IC2") (pin "2") (pinfunction "GND_2") (pintype "passive"))
      (node (ref "IC3") (pin "2") (pinfunction "GND_2") (pintype "passive"))
      (node (ref "IC4") (pin "3") (pinfunction "ON*/OFF_3") (pintype "bidirectional"))
      (node (ref "IC4") (pin "5") (pinfunction "GND_5") (pintype "bidirectional"))
      (node (ref "IC5") (pin "3") (pinfunction "ON*/OFF_3") (pintype "bidirectional"))
      (node (ref "IC5") (pin "5") (pinfunction "GND_5") (pintype "bidirectional"))
      (node (ref "IC6") (pin "4") (pinfunction "V-_4") (pintype "power_in"))
      (node (ref "LIPO") (pin "P$2") (pinfunction "P$2_P$2") (pintype "bidirectional"))
      (node (ref "PWROUT1") (pin "P$2") (pinfunction "P$2_P$2") (pintype "bidirectional"))
      (node (ref "PWROUT2") (pin "P$2") (pinfunction "P$2_P$2") (pintype "bidirectional"))
      (node (ref "PWROUT3") (pin "P$2") (pinfunction "P$2_P$2") (pintype "bidirectional"))
      (node (ref "PWROUT4") (pin "P$2") (pinfunction "P$2_P$2") (pintype "bidirectional"))
      (node (ref "Q1") (pin "S") (pinfunction "S_S") (pintype "passive"))
      (node (ref "Q2") (pin "S") (pinfunction "S_S") (pintype "passive"))
      (node (ref "R1") (pin "1") (pinfunction "1_1") (pintype "passive"))
      (node (ref "R10") (pin "1") (pinfunction "1_1") (pintype "passive"))
      (node (ref "R11") (pin "A") (pinfunction "A_A") (pintype "passive"))
      (node (ref "R12") (pin "A") (pinfunction "A_A") (pintype "passive"))
      (node (ref "R14") (pin "1") (pinfunction "1_1") (pintype "passive"))
      (node (ref "R16") (pin "1") (pinfunction "1_1") (pintype "passive"))
      (node (ref "R2") (pin "1") (pinfunction "1_1") (pintype "passive"))
      (node (ref "R3") (pin "1") (pinfunction "1_1") (pintype "passive"))
      (node (ref "R4") (pin "1") (pinfunction "1_1") (pintype "passive"))
      (node (ref "R5") (pin "1") (pinfunction "1_1") (pintype "passive"))
      (node (ref "R6") (pin "1") (pinfunction "1_1") (pintype "passive"))
      (node (ref "R7") (pin "1") (pinfunction "1_1") (pintype "passive"))
      (node (ref "R8") (pin "1") (pinfunction "1_1") (pintype "passive"))
      (node (ref "R9") (pin "1") (pinfunction "1_1") (pintype "passive"))
      (node (ref "S18") (pin "B1") (pinfunction "2_B1") (pintype "bidirectional"))
      (node (ref "S18") (pin "B2") (pinfunction "2_B2") (pintype "bidirectional"))
      (node (ref "S9") (pin "B1") (pinfunction "2_B1") (pintype "bidirectional"))
      (node (ref "S9") (pin "B2") (pinfunction "2_B2") (pintype "bidirectional"))
      (node (ref "U$1") (pin "GND") (pinfunction "GND_GND") (pintype "power_in"))
      (node (ref "U$1") (pin "GND1") (pinfunction "GND_GND1") (pintype "power_in"))
      (node (ref "U$1") (pin "GND2") (pinfunction "GND_GND2") (pintype "power_in"))
      (node (ref "U1") (pin "2") (pinfunction "GND_2") (pintype "input"))
      (node (ref "U2") (pin "2") (pinfunction "GND_2") (pintype "input"))
    )
    (net (code "52") (name "LOWVIN") (class "Default")
      (node (ref "B-REG") (pin "B1") (pinfunction "2_B1") (pintype "bidirectional"))
      (node (ref "B-REG") (pin "B2") (pinfunction "2_B2") (pintype "bidirectional"))
      (node (ref "C14") (pin "+") (pinfunction "+_+") (pintype "passive"))
      (node (ref "L4") (pin "1") (pinfunction "1_1") (pintype "passive"))
      (node (ref "U2") (pin "1") (pinfunction "VIN_1") (pintype "input"))
      (node (ref "U2") (pin "3") (pinfunction "EN_3") (pintype "input"))
    )
    (net (code "53") (name "Net-(C1-Pad+)") (class "Default")
      (node (ref "C1") (pin "+") (pinfunction "+_+") (pintype "passive"))
      (node (ref "D1") (pin "A") (pinfunction "A_A") (pintype "passive"))
      (node (ref "D2") (pin "A") (pinfunction "A_A") (pintype "passive"))
      (node (ref "LIPO") (pin "P$1") (pinfunction "P$1_P$1") (pintype "bidirectional"))
    )
    (net (code "54") (name "Net-(D1-PadC)") (class "Default")
      (node (ref "D1") (pin "C") (pinfunction "C_C") (pintype "passive"))
      (node (ref "SWITCH") (pin "P$2") (pinfunction "P$2_P$2") (pintype "bidirectional"))
    )
    (net (code "55") (name "Net-(D2-C)") (class "Default")
      (node (ref "D2") (pin "K") (pinfunction "C_K") (pintype "passive"))
      (node (ref "R1") (pin "2") (pinfunction "2_2") (pintype "passive"))
    )
    (net (code "56") (name "Net-(D3-C)") (class "Default")
      (node (ref "D3") (pin "K") (pinfunction "C_K") (pintype "passive"))
      (node (ref "R2") (pin "2") (pinfunction "2_2") (pintype "passive"))
    )
    (net (code "57") (name "Net-(D4-C)") (class "Default")
      (node (ref "D4") (pin "K") (pinfunction "C_K") (pintype "passive"))
      (node (ref "R3") (pin "2") (pinfunction "2_2") (pintype "passive"))
    )
    (net (code "58") (name "Net-(D5-C)") (class "Default")
      (node (ref "D5") (pin "K") (pinfunction "C_K") (pintype "passive"))
      (node (ref "R4") (pin "2") (pinfunction "2_2") (pintype "passive"))
    )
    (net (code "59") (name "Net-(D6-C)") (class "Default")
      (node (ref "D6") (pin "K") (pinfunction "C_K") (pintype "passive"))
      (node (ref "R8") (pin "2") (pinfunction "2_2") (pintype "passive"))
    )
    (net (code "60") (name "Net-(D6-PadA)") (class "Default")
      (node (ref "D6") (pin "A") (pinfunction "A_A") (pintype "passive"))
      (node (ref "FUSE4") (pin "P$1") (pinfunction "P$1_P$1") (pintype "bidirectional"))
      (node (ref "PWROUT4") (pin "P$1") (pinfunction "P$1_P$1") (pintype "bidirectional"))
    )
    (net (code "61") (name "Net-(D7-C)") (class "Default")
      (node (ref "D7") (pin "K") (pinfunction "C_K") (pintype "passive"))
      (node (ref "R5") (pin "2") (pinfunction "2_2") (pintype "passive"))
    )
    (net (code "62") (name "Net-(D7-PadA)") (class "Default")
      (node (ref "D7") (pin "A") (pinfunction "A_A") (pintype "passive"))
      (node (ref "FUSE3") (pin "P$1") (pinfunction "P$1_P$1") (pintype "bidirectional"))
      (node (ref "PWROUT3") (pin "P$1") (pinfunction "P$1_P$1") (pintype "bidirectional"))
    )
    (net (code "63") (name "Net-(D8-C)") (class "Default")
      (node (ref "D8") (pin "K") (pinfunction "C_K") (pintype "passive"))
      (node (ref "R6") (pin "2") (pinfunction "2_2") (pintype "passive"))
    )
    (net (code "64") (name "Net-(D8-PadA)") (class "Default")
      (node (ref "D8") (pin "A") (pinfunction "A_A") (pintype "passive"))
      (node (ref "FUSE2") (pin "P$1") (pinfunction "P$1_P$1") (pintype "bidirectional"))
      (node (ref "PWROUT2") (pin "P$1") (pinfunction "P$1_P$1") (pintype "bidirectional"))
    )
    (net (code "65") (name "Net-(D9-C)") (class "Default")
      (node (ref "D9") (pin "K") (pinfunction "C_K") (pintype "passive"))
      (node (ref "R7") (pin "2") (pinfunction "2_2") (pintype "passive"))
    )
    (net (code "66") (name "Net-(D9-PadA)") (class "Default")
      (node (ref "D9") (pin "A") (pinfunction "A_A") (pintype "passive"))
      (node (ref "FUSE1") (pin "P$1") (pinfunction "P$1_P$1") (pintype "bidirectional"))
      (node (ref "PWROUT1") (pin "P$1") (pinfunction "P$1_P$1") (pintype "bidirectional"))
    )
    (net (code "67") (name "Net-(D13-C)") (class "Default")
      (node (ref "D13") (pin "K") (pinfunction "C_K") (pintype "passive"))
      (node (ref "R9") (pin "2") (pinfunction "2_2") (pintype "passive"))
    )
    (net (code "68") (name "Net-(D14-C)") (class "Default")
      (node (ref "D14") (pin "K") (pinfunction "C_K") (pintype "passive"))
      (node (ref "R10") (pin "2") (pinfunction "2_2") (pintype "passive"))
    )
    (net (code "69") (name "Net-(IC4-OUT)") (class "Default")
      (node (ref "D10") (pin "+") (pinfunction "+_+") (pintype "bidirectional"))
      (node (ref "IC4") (pin "2") (pinfunction "OUT_2") (pintype "bidirectional"))
      (node (ref "L1") (pin "1") (pinfunction "1_1") (pintype "passive"))
    )
    (net (code "70") (name "Net-(IC5-OUT)") (class "Default")
      (node (ref "D11") (pin "+") (pinfunction "+_+") (pintype "bidirectional"))
      (node (ref "IC5") (pin "2") (pinfunction "OUT_2") (pintype "bidirectional"))
      (node (ref "L2") (pin "1") (pinfunction "1_1") (pintype "passive"))
    )
    (net (code "71") (name "Net-(IC6A--IN)") (class "Default")
      (node (ref "IC6") (pin "2") (pinfunction "-IN_2") (pintype "input"))
      (node (ref "R13") (pin "1") (pinfunction "1_1") (pintype "passive"))
      (node (ref "R14") (pin "2") (pinfunction "2_2") (pintype "passive"))
    )
    (net (code "72") (name "Net-(IC6A-OUT)") (class "Default")
      (node (ref "IC6") (pin "1") (pinfunction "OUT_1") (pintype "output"))
      (node (ref "Q1") (pin "G") (pinfunction "G_G") (pintype "passive"))
    )
    (net (code "73") (name "Net-(IC6B--IN)") (class "Default")
      (node (ref "IC6") (pin "6") (pinfunction "-IN_6") (pintype "input"))
      (node (ref "R15") (pin "1") (pinfunction "1_1") (pintype "passive"))
      (node (ref "R16") (pin "2") (pinfunction "2_2") (pintype "passive"))
    )
    (net (code "74") (name "Net-(IC6B-OUT)") (class "Default")
      (node (ref "IC6") (pin "7") (pinfunction "OUT_7") (pintype "output"))
      (node (ref "Q2") (pin "G") (pinfunction "G_G") (pintype "passive"))
    )
    (net (code "75") (name "Net-(U1-FB)") (class "Default")
      (node (ref "3V3LDO") (pin "A1") (pinfunction "1_A1") (pintype "bidirectional"))
      (node (ref "3V3LDO") (pin "A2") (pinfunction "1_A2") (pintype "bidirectional"))
      (node (ref "C13") (pin "+") (pinfunction "+_+") (pintype "passive"))
      (node (ref "L3") (pin "2") (pinfunction "2_2") (pintype "passive"))
      (node (ref "U1") (pin "4") (pinfunction "FB_4") (pintype "input"))
    )
    (net (code "76") (name "Net-(U1-SW)") (class "Default")
      (node (ref "L3") (pin "1") (pinfunction "1_1") (pintype "passive"))
      (node (ref "U1") (pin "5") (pinfunction "SW_5") (pintype "passive"))
    )
    (net (code "77") (name "Net-(U2-L)") (class "Default")
      (node (ref "L4") (pin "2") (pinfunction "2_2") (pintype "passive"))
      (node (ref "U2") (pin "5") (pinfunction "L_5") (pintype "passive"))
    )
    (net (code "78") (name "PGM") (class "Default")
      (node (ref "S13") (pin "A1") (pinfunction "1_A1") (pintype "bidirectional"))
      (node (ref "S13") (pin "A2") (pinfunction "1_A2") (pintype "bidirectional"))
      (node (ref "U$1") (pin "PGM") (pinfunction "PGM_PGM") (pintype "bidirectional"))
    )
    (net (code "79") (name "POTIN1") (class "Default")
      (node (ref "POT1") (pin "A1") (pinfunction "1_A1") (pintype "bidirectional"))
      (node (ref "POT1") (pin "A2") (pinfunction "1_A2") (pintype "bidirectional"))
      (node (ref "R11") (pin "E") (pinfunction "E_E") (pintype "passive"))
    )
    (net (code "80") (name "POTIN2") (class "Default")
      (node (ref "POT2") (pin "A1") (pinfunction "1_A1") (pintype "bidirectional"))
      (node (ref "POT2") (pin "A2") (pinfunction "1_A2") (pintype "bidirectional"))
      (node (ref "R12") (pin "E") (pinfunction "E_E") (pintype "passive"))
    )
    (net (code "81") (name "POTOUT1") (class "Default")
      (node (ref "POT1") (pin "B1") (pinfunction "2_B1") (pintype "bidirectional"))
      (node (ref "POT1") (pin "B2") (pinfunction "2_B2") (pintype "bidirectional"))
      (node (ref "R11") (pin "S") (pinfunction "S_S") (pintype "passive"))
    )
    (net (code "82") (name "POTOUT2") (class "Default")
      (node (ref "POT2") (pin "B1") (pinfunction "2_B1") (pintype "bidirectional"))
      (node (ref "POT2") (pin "B2") (pinfunction "2_B2") (pintype "bidirectional"))
      (node (ref "R12") (pin "S") (pinfunction "S_S") (pintype "passive"))
    )
    (net (code "83") (name "TRG1") (class "Default")
      (node (ref "DCVCTRL") (pin "A1") (pinfunction "1_A1") (pintype "bidirectional"))
      (node (ref "DCVCTRL") (pin "A2") (pinfunction "1_A2") (pintype "bidirectional"))
      (node (ref "IC6") (pin "3") (pinfunction "+IN_3") (pintype "input"))
    )
    (net (code "84") (name "TRG2") (class "Default")
      (node (ref "DCVCTRL") (pin "B1") (pinfunction "2_B1") (pintype "bidirectional"))
      (node (ref "DCVCTRL") (pin "B2") (pinfunction "2_B2") (pintype "bidirectional"))
      (node (ref "IC6") (pin "5") (pinfunction "+IN_5") (pintype "input"))
    )
    (net (code "85") (name "VBAT") (class "Default")
      (node (ref "S17") (pin "B1") (pinfunction "2_B1") (pintype "bidirectional"))
      (node (ref "S17") (pin "B2") (pinfunction "2_B2") (pintype "bidirectional"))
      (node (ref "U$1") (pin "VBAT") (pinfunction "VBAT_VBAT") (pintype "power_in"))
    )
    (net (code "86") (name "VCC") (class "Default")
      (node (ref "C2") (pin "+") (pinfunction "+_+") (pintype "passive"))
      (node (ref "C4") (pin "+") (pinfunction "+_+") (pintype "passive"))
      (node (ref "C6") (pin "+") (pinfunction "+_+") (pintype "passive"))
      (node (ref "C8") (pin "+") (pinfunction "+_+") (pintype "passive"))
      (node (ref "C9") (pin "+") (pinfunction "+_+") (pintype "passive"))
      (node (ref "FUSE1") (pin "P$2") (pinfunction "P$2_P$2") (pintype "bidirectional"))
      (node (ref "FUSE2") (pin "P$2") (pinfunction "P$2_P$2") (pintype "bidirectional"))
      (node (ref "FUSE3") (pin "P$2") (pinfunction "P$2_P$2") (pintype "bidirectional"))
      (node (ref "FUSE4") (pin "P$2") (pinfunction "P$2_P$2") (pintype "bidirectional"))
      (node (ref "IC1") (pin "1") (pinfunction "VI_1") (pintype "input"))
      (node (ref "IC2") (pin "1") (pinfunction "VI_1") (pintype "input"))
      (node (ref "IC3") (pin "1") (pinfunction "VI_1") (pintype "input"))
      (node (ref "IC4") (pin "1") (pinfunction "IN_1") (pintype "bidirectional"))
      (node (ref "IC5") (pin "1") (pinfunction "IN_1") (pintype "bidirectional"))
      (node (ref "SWITCH") (pin "P$1") (pinfunction "P$1_P$1") (pintype "bidirectional"))
    )
    (net (code "87") (name "VUSB") (class "Default")
      (node (ref "S14") (pin "B1") (pinfunction "2_B1") (pintype "bidirectional"))
      (node (ref "S14") (pin "B2") (pinfunction "2_B2") (pintype "bidirectional"))
      (node (ref "U$1") (pin "VUSB") (pinfunction "VUSB_VUSB") (pintype "power_in"))
    )
  )
)
